# ETHERNET.net
KiCad netlist of a schematic drawn in Altium Designer
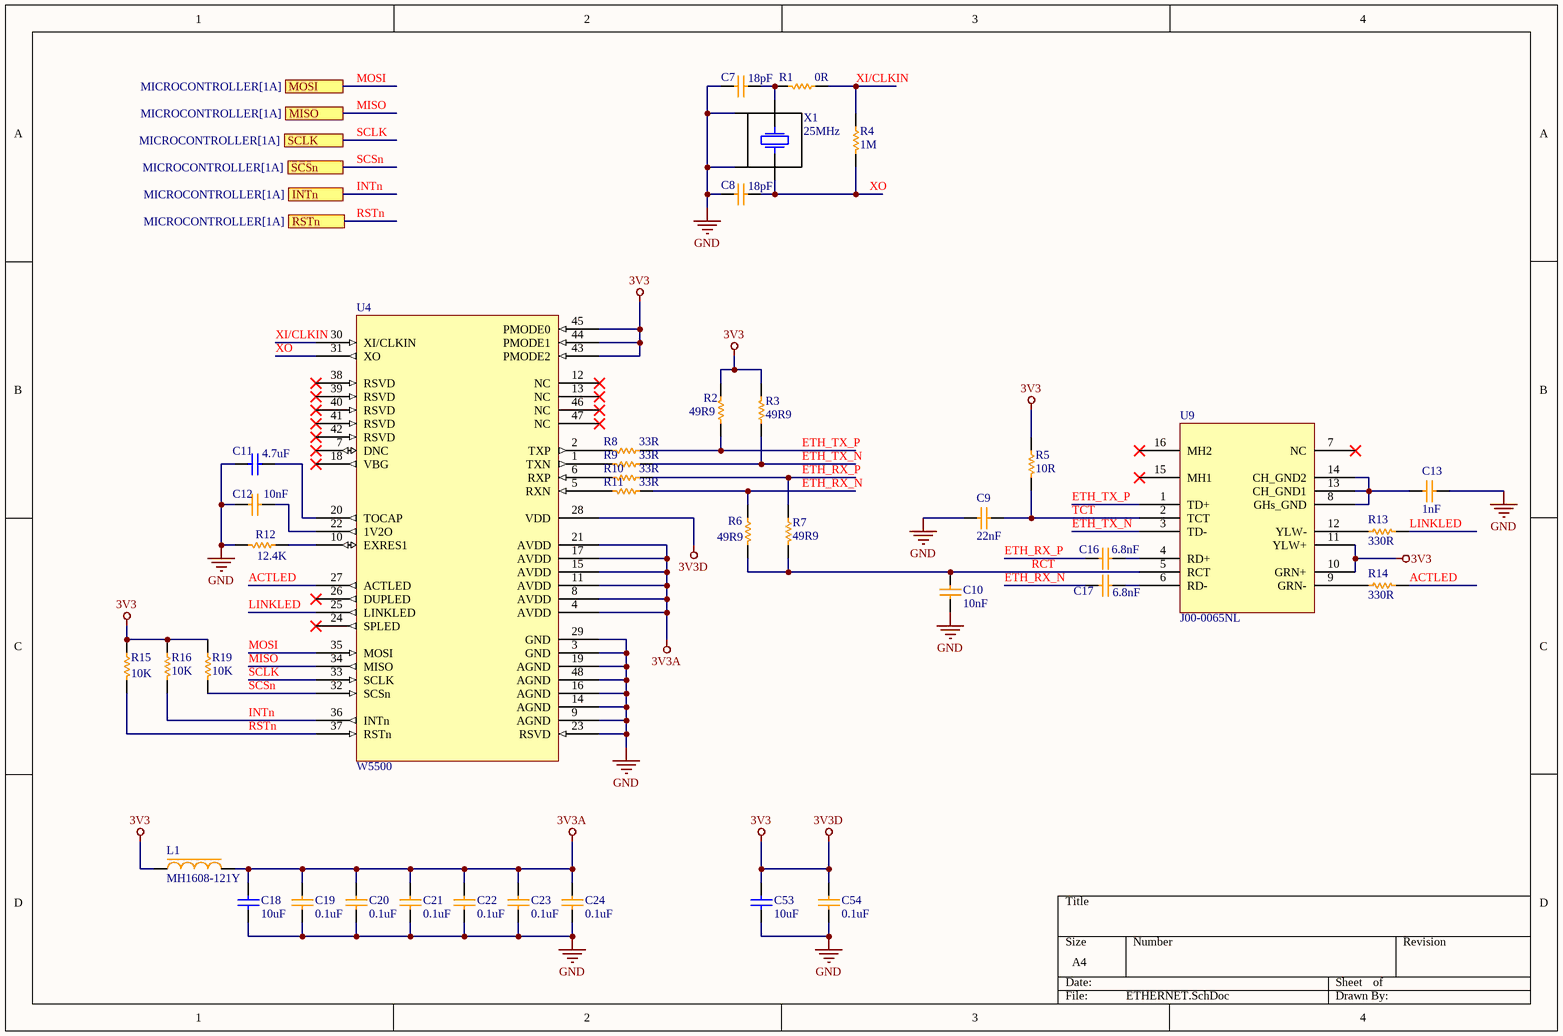
[diagram p0: ETHERNET.SchDoc]

(export (version "E")
  (design (tool "Eeschema 10.0.6"))
  (components
    (comp (ref "C7")
      (value "18pF")
      (footprint "CAP-0603")
      (description "CAP CER 18PF 50V C0G/NP0 0603")
      (libsource (lib "Schlib1") (part "CAP-0603"))
    )
    (comp (ref "C8")
      (value "18pF")
      (footprint "CAP-0603")
      (description "CAP CER 18PF 50V C0G/NP0 0603")
      (libsource (lib "Schlib1") (part "CAP-0603"))
    )
    (comp (ref "C9")
      (value "22nF")
      (footprint "CAP-0603")
      (description "CAP CER 22NF 50V X7R 0603")
      (libsource (lib "Schlib1") (part "CAP-0603"))
    )
    (comp (ref "C10")
      (value "10nF")
      (footprint "CAP-0603")
      (description "CAP CER 1ONF 50V X7R 0603")
      (libsource (lib "Schlib1") (part "CAP-0603"))
    )
    (comp (ref "C11")
      (value "4.7uF")
      (footprint "CAP-0805")
      (description "CAP CER 4.7UF 16V X7R 0805")
      (libsource (lib "Schlib1") (part "CAP-0805"))
    )
    (comp (ref "C12")
      (value "10nF")
      (footprint "CAP-0603")
      (description "CAP CER 1ONF 50V X7R 0603")
      (libsource (lib "Schlib1") (part "CAP-0603"))
    )
    (comp (ref "C13")
      (value "1nF")
      (footprint "CAP-0603")
      (description "CAP CER 1NF 2000V X7R 0603")
      (libsource (lib "Schlib1") (part "CAP-0603"))
    )
    (comp (ref "C16")
      (value "6.8nF")
      (footprint "CAP-0603")
      (description "CAP CER 6800PF 50V X7R 0603")
      (libsource (lib "Schlib1") (part "CAP-0603"))
    )
    (comp (ref "C17")
      (value "6.8nF")
      (footprint "CAP-0603")
      (description "CAP CER 6800PF 50V X7R 0603")
      (libsource (lib "Schlib1") (part "CAP-0603"))
    )
    (comp (ref "C18")
      (value "10uF")
      (footprint "CAP-0805")
      (description "CAP CER 10UF 16V X5R 0805")
      (libsource (lib "Schlib1") (part "CAP-0805"))
    )
    (comp (ref "C19")
      (value "0.1uF")
      (footprint "CAP-0603")
      (description "CAP CER 0.1UF 50V X7R 0603")
      (libsource (lib "Schlib1") (part "CAP-0603"))
    )
    (comp (ref "C20")
      (value "0.1uF")
      (footprint "CAP-0603")
      (description "CAP CER 0.1UF 50V X7R 0603")
      (libsource (lib "Schlib1") (part "CAP-0603"))
    )
    (comp (ref "C21")
      (value "0.1uF")
      (footprint "CAP-0603")
      (description "CAP CER 0.1UF 50V X7R 0603")
      (libsource (lib "Schlib1") (part "CAP-0603"))
    )
    (comp (ref "C22")
      (value "0.1uF")
      (footprint "CAP-0603")
      (description "CAP CER 0.1UF 50V X7R 0603")
      (libsource (lib "Schlib1") (part "CAP-0603"))
    )
    (comp (ref "C23")
      (value "0.1uF")
      (footprint "CAP-0603")
      (description "CAP CER 0.1UF 50V X7R 0603")
      (libsource (lib "Schlib1") (part "CAP-0603"))
    )
    (comp (ref "C24")
      (value "0.1uF")
      (footprint "CAP-0603")
      (description "CAP CER 0.1UF 50V X7R 0603")
      (libsource (lib "Schlib1") (part "CAP-0603"))
    )
    (comp (ref "C53")
      (value "10uF")
      (footprint "CAP-0805")
      (description "CAP CER 10UF 16V X5R 0805")
      (libsource (lib "Schlib1") (part "CAP-0805"))
    )
    (comp (ref "C54")
      (value "0.1uF")
      (footprint "CAP-0603")
      (description "CAP CER 0.1UF 50V X7R 0603")
      (libsource (lib "Schlib1") (part "CAP-0603"))
    )
    (comp (ref "L1")
      (value "MH1608-121Y")
      (footprint "FB-0603")
      (description "FERRITE BEAD 120 OHM 0603 1LN")
      (libsource (lib "schematic") (part "FB-0603"))
    )
    (comp (ref "R1")
      (value "0R")
      (footprint "RES-0603")
      (description "RES SMD 0 OHM JUMPER 1/10W 0603")
      (libsource (lib "Schlib1") (part "RES-0603"))
    )
    (comp (ref "R2")
      (value "49R9")
      (footprint "RES-0603")
      (description "RES SMD 49.9 OHM 1% 1/10W 0603")
      (libsource (lib "Schlib1") (part "RES-0603"))
    )
    (comp (ref "R3")
      (value "49R9")
      (footprint "RES-0603")
      (description "RES SMD 49.9 OHM 1% 1/10W 0603")
      (libsource (lib "Schlib1") (part "RES-0603"))
    )
    (comp (ref "R4")
      (value "1M")
      (footprint "RES-0603")
      (description "RES SMD 1M OHM 1% 1/10W 0603")
      (libsource (lib "Schlib1") (part "RES-0603"))
    )
    (comp (ref "R5")
      (value "10R")
      (footprint "RES-0603")
      (description "RES SMD 10 OHM 1% 1/10W 0603")
      (libsource (lib "Schlib1") (part "RES-0603"))
    )
    (comp (ref "R6")
      (value "49R9")
      (footprint "RES-0603")
      (description "RES SMD 49.9 OHM 1% 1/10W 0603")
      (libsource (lib "Schlib1") (part "RES-0603"))
    )
    (comp (ref "R7")
      (value "49R9")
      (footprint "RES-0603")
      (description "RES SMD 49.9 OHM 1% 1/10W 0603")
      (libsource (lib "Schlib1") (part "RES-0603"))
    )
    (comp (ref "R8")
      (value "33R")
      (footprint "RES-0603")
      (description "RES SMD 33 OHM 1% 1/10W 0603")
      (libsource (lib "Schlib1") (part "RES-0603"))
    )
    (comp (ref "R9")
      (value "33R")
      (footprint "RES-0603")
      (description "RES SMD 33 OHM 1% 1/10W 0603")
      (libsource (lib "Schlib1") (part "RES-0603"))
    )
    (comp (ref "R10")
      (value "33R")
      (footprint "RES-0603")
      (description "RES SMD 33 OHM 1% 1/10W 0603")
      (libsource (lib "Schlib1") (part "RES-0603"))
    )
    (comp (ref "R11")
      (value "33R")
      (footprint "RES-0603")
      (description "RES SMD 33 OHM 1% 1/10W 0603")
      (libsource (lib "Schlib1") (part "RES-0603"))
    )
    (comp (ref "R12")
      (value "12.4K")
      (footprint "RES-0603")
      (description "RES SMD 12.4K OHM 1% 1/10W 0603")
      (libsource (lib "Schlib1") (part "RES-0603"))
    )
    (comp (ref "R13")
      (value "330R")
      (footprint "RES-0603")
      (description "RES SMD 330 OHM 5% 1/10W 0603")
      (libsource (lib "Schlib1") (part "RES-0603"))
    )
    (comp (ref "R14")
      (value "330R")
      (footprint "RES-0603")
      (description "RES SMD 330 OHM 5% 1/10W 0603")
      (libsource (lib "Schlib1") (part "RES-0603"))
    )
    (comp (ref "R15")
      (value "10K")
      (footprint "RES-0603")
      (description "RES SMD 10K OHM 5% 1/10W 0603")
      (libsource (lib "Schlib1") (part "RES-0603"))
    )
    (comp (ref "R16")
      (value "10K")
      (footprint "RES-0603")
      (description "RES SMD 10K OHM 5% 1/10W 0603")
      (libsource (lib "Schlib1") (part "RES-0603"))
    )
    (comp (ref "R19")
      (value "10K")
      (footprint "RES-0603")
      (description "RES SMD 10K OHM 5% 1/10W 0603")
      (libsource (lib "Schlib1") (part "RES-0603"))
    )
    (comp (ref "U4")
      (value "W5500")
      (footprint "48LQFP")
      (description "IC CTLR 3-1 ETH TCP/IP 48LQFP")
      (libsource (lib "schematic") (part "W5500"))
    )
    (comp (ref "U9")
      (value "J00-0065NL")
      (footprint "J00-0065NL")
      (description "CONN JACK 1PORT PCB")
      (libsource (lib "schematic") (part "J00-0065NL"))
    )
    (comp (ref "X1")
      (value "25MHz")
      (footprint "CRYSTAL-2520")
      (description "122M4-25.000F13DWNJK\r\n(2520,25MHz,13pF,10ppm,-40-105,30)")
      (libsource (lib "Schlib1") (part "CRYSTAL-2520"))
    )
  )
  (nets
    (net (code "1") (name "/ACTLED") (class "Default")
      (node (ref "R14") (pin "1") (pinfunction "1_1") (pintype "passive"))
      (node (ref "U4") (pin "27") (pinfunction "ACTLED_27") (pintype "output"))
    )
    (net (code "2") (name "/ETH_RX_N") (class "Default")
      (node (ref "C17") (pin "1") (pinfunction "1_1") (pintype "passive"))
      (node (ref "R11") (pin "2") (pinfunction "2_2") (pintype "passive"))
      (node (ref "R6") (pin "2") (pinfunction "2_2") (pintype "passive"))
    )
    (net (code "3") (name "/ETH_RX_P") (class "Default")
      (node (ref "C16") (pin "1") (pinfunction "1_1") (pintype "passive"))
      (node (ref "R10") (pin "2") (pinfunction "2_2") (pintype "passive"))
      (node (ref "R7") (pin "2") (pinfunction "2_2") (pintype "passive"))
    )
    (net (code "4") (name "/ETH_TX_N") (class "Default")
      (node (ref "R3") (pin "2") (pinfunction "2_2") (pintype "passive"))
      (node (ref "R9") (pin "2") (pinfunction "2_2") (pintype "passive"))
      (node (ref "U9") (pin "3") (pinfunction "TD-_3") (pintype "passive"))
    )
    (net (code "5") (name "/ETH_TX_P") (class "Default")
      (node (ref "R2") (pin "2") (pinfunction "2_2") (pintype "passive"))
      (node (ref "R8") (pin "2") (pinfunction "2_2") (pintype "passive"))
      (node (ref "U9") (pin "1") (pinfunction "TD+_1") (pintype "passive"))
    )
    (net (code "6") (name "/INTn") (class "Default")
      (node (ref "R16") (pin "1") (pinfunction "1_1") (pintype "passive"))
      (node (ref "U4") (pin "36") (pinfunction "INTn_36") (pintype "output"))
    )
    (net (code "7") (name "/LINKLED") (class "Default")
      (node (ref "R13") (pin "1") (pinfunction "1_1") (pintype "passive"))
      (node (ref "U4") (pin "25") (pinfunction "LINKLED_25") (pintype "output"))
    )
    (net (code "8") (name "/MISO") (class "Default")
      (node (ref "U4") (pin "34") (pinfunction "MISO_34") (pintype "output"))
    )
    (net (code "9") (name "/MOSI") (class "Default")
      (node (ref "U4") (pin "35") (pinfunction "MOSI_35") (pintype "input"))
    )
    (net (code "10") (name "/RCT") (class "Default")
      (node (ref "C10") (pin "2") (pinfunction "2_2") (pintype "passive"))
      (node (ref "R6") (pin "1") (pinfunction "1_1") (pintype "passive"))
      (node (ref "R7") (pin "1") (pinfunction "1_1") (pintype "passive"))
      (node (ref "U9") (pin "5") (pinfunction "RCT_5") (pintype "passive"))
    )
    (net (code "11") (name "/RSTn") (class "Default")
      (node (ref "R15") (pin "1") (pinfunction "1_1") (pintype "passive"))
      (node (ref "U4") (pin "37") (pinfunction "RSTn_37") (pintype "input"))
    )
    (net (code "12") (name "/SCLK") (class "Default")
      (node (ref "U4") (pin "33") (pinfunction "SCLK_33") (pintype "input"))
    )
    (net (code "13") (name "/SCSn") (class "Default")
      (node (ref "R19") (pin "1") (pinfunction "1_1") (pintype "passive"))
      (node (ref "U4") (pin "32") (pinfunction "SCSn_32") (pintype "input"))
    )
    (net (code "14") (name "/TCT") (class "Default")
      (node (ref "C9") (pin "1") (pinfunction "1_1") (pintype "passive"))
      (node (ref "R5") (pin "1") (pinfunction "1_1") (pintype "passive"))
      (node (ref "U9") (pin "2") (pinfunction "TCT_2") (pintype "passive"))
    )
    (net (code "15") (name "/XI{slash}CLKIN") (class "Default")
      (node (ref "R1") (pin "2") (pinfunction "2_2") (pintype "passive"))
      (node (ref "R4") (pin "2") (pinfunction "2_2") (pintype "passive"))
      (node (ref "U4") (pin "30") (pinfunction "XI/CLKIN_30") (pintype "input"))
    )
    (net (code "16") (name "/XO") (class "Default")
      (node (ref "C8") (pin "2") (pinfunction "2_2") (pintype "passive"))
      (node (ref "R4") (pin "1") (pinfunction "1_1") (pintype "passive"))
      (node (ref "U4") (pin "31") (pinfunction "XO_31") (pintype "output"))
      (node (ref "X1") (pin "3") (pinfunction "3_3") (pintype "passive"))
    )
    (net (code "17") (name "3V3") (class "Default")
      (node (ref "C53") (pin "2") (pinfunction "2_2") (pintype "passive"))
      (node (ref "C54") (pin "2") (pinfunction "2_2") (pintype "passive"))
      (node (ref "L1") (pin "1") (pinfunction "1_1") (pintype "passive"))
      (node (ref "R15") (pin "2") (pinfunction "2_2") (pintype "passive"))
      (node (ref "R16") (pin "2") (pinfunction "2_2") (pintype "passive"))
      (node (ref "R19") (pin "2") (pinfunction "2_2") (pintype "passive"))
      (node (ref "R2") (pin "1") (pinfunction "1_1") (pintype "passive"))
      (node (ref "R3") (pin "1") (pinfunction "1_1") (pintype "passive"))
      (node (ref "R5") (pin "2") (pinfunction "2_2") (pintype "passive"))
      (node (ref "U4") (pin "28") (pinfunction "VDD_28") (pintype "power_in"))
      (node (ref "U4") (pin "43") (pinfunction "PMODE2_43") (pintype "input"))
      (node (ref "U4") (pin "44") (pinfunction "PMODE1_44") (pintype "input"))
      (node (ref "U4") (pin "45") (pinfunction "PMODE0_45") (pintype "input"))
      (node (ref "U9") (pin "10") (pinfunction "GRN+_10") (pintype "passive"))
      (node (ref "U9") (pin "11") (pinfunction "YLW+_11") (pintype "passive"))
    )
    (net (code "18") (name "3V3A") (class "Default")
      (node (ref "C18") (pin "2") (pinfunction "2_2") (pintype "passive"))
      (node (ref "C19") (pin "2") (pinfunction "2_2") (pintype "passive"))
      (node (ref "C20") (pin "2") (pinfunction "2_2") (pintype "passive"))
      (node (ref "C21") (pin "2") (pinfunction "2_2") (pintype "passive"))
      (node (ref "C22") (pin "2") (pinfunction "2_2") (pintype "passive"))
      (node (ref "C23") (pin "2") (pinfunction "2_2") (pintype "passive"))
      (node (ref "C24") (pin "2") (pinfunction "2_2") (pintype "passive"))
      (node (ref "L1") (pin "2") (pinfunction "2_2") (pintype "passive"))
      (node (ref "U4") (pin "11") (pinfunction "AVDD_11") (pintype "power_in"))
      (node (ref "U4") (pin "15") (pinfunction "AVDD_15") (pintype "power_in"))
      (node (ref "U4") (pin "17") (pinfunction "AVDD_17") (pintype "power_in"))
      (node (ref "U4") (pin "21") (pinfunction "AVDD_21") (pintype "power_in"))
      (node (ref "U4") (pin "4") (pinfunction "AVDD_4") (pintype "power_in"))
      (node (ref "U4") (pin "8") (pinfunction "AVDD_8") (pintype "power_in"))
    )
    (net (code "19") (name "GND") (class "Default")
      (node (ref "C10") (pin "1") (pinfunction "1_1") (pintype "passive"))
      (node (ref "C11") (pin "1") (pinfunction "1_1") (pintype "passive"))
      (node (ref "C12") (pin "2") (pinfunction "2_2") (pintype "passive"))
      (node (ref "C13") (pin "2") (pinfunction "2_2") (pintype "passive"))
      (node (ref "C18") (pin "1") (pinfunction "1_1") (pintype "passive"))
      (node (ref "C19") (pin "1") (pinfunction "1_1") (pintype "passive"))
      (node (ref "C20") (pin "1") (pinfunction "1_1") (pintype "passive"))
      (node (ref "C21") (pin "1") (pinfunction "1_1") (pintype "passive"))
      (node (ref "C22") (pin "1") (pinfunction "1_1") (pintype "passive"))
      (node (ref "C23") (pin "1") (pinfunction "1_1") (pintype "passive"))
      (node (ref "C24") (pin "1") (pinfunction "1_1") (pintype "passive"))
      (node (ref "C53") (pin "1") (pinfunction "1_1") (pintype "passive"))
      (node (ref "C54") (pin "1") (pinfunction "1_1") (pintype "passive"))
      (node (ref "C7") (pin "1") (pinfunction "1_1") (pintype "passive"))
      (node (ref "C8") (pin "1") (pinfunction "1_1") (pintype "passive"))
      (node (ref "C9") (pin "2") (pinfunction "2_2") (pintype "passive"))
      (node (ref "R12") (pin "1") (pinfunction "1_1") (pintype "passive"))
      (node (ref "U4") (pin "14") (pinfunction "AGND_14") (pintype "power_in"))
      (node (ref "U4") (pin "16") (pinfunction "AGND_16") (pintype "power_in"))
      (node (ref "U4") (pin "19") (pinfunction "AGND_19") (pintype "power_in"))
      (node (ref "U4") (pin "23") (pinfunction "RSVD_23") (pintype "input"))
      (node (ref "U4") (pin "29") (pinfunction "GND_29") (pintype "power_in"))
      (node (ref "U4") (pin "3") (pinfunction "GND_3") (pintype "power_in"))
      (node (ref "U4") (pin "48") (pinfunction "AGND_48") (pintype "power_in"))
      (node (ref "U4") (pin "9") (pinfunction "AGND_9") (pintype "power_in"))
      (node (ref "X1") (pin "2") (pinfunction "2_2") (pintype "passive"))
      (node (ref "X1") (pin "4") (pinfunction "4_4") (pintype "passive"))
    )
    (net (code "20") (name "Net-(C7-Pad2)") (class "Default")
      (node (ref "C7") (pin "2") (pinfunction "2_2") (pintype "passive"))
      (node (ref "R1") (pin "1") (pinfunction "1_1") (pintype "passive"))
      (node (ref "X1") (pin "1") (pinfunction "1_1") (pintype "passive"))
    )
    (net (code "21") (name "Net-(U4-1V2O)") (class "Default")
      (node (ref "C12") (pin "1") (pinfunction "1_1") (pintype "passive"))
      (node (ref "U4") (pin "22") (pinfunction "1V2O_22") (pintype "output"))
    )
    (net (code "22") (name "Net-(U4-EXRES1)") (class "Default")
      (node (ref "R12") (pin "2") (pinfunction "2_2") (pintype "passive"))
      (node (ref "U4") (pin "10") (pinfunction "EXRES1_10") (pintype "bidirectional"))
    )
    (net (code "23") (name "Net-(U4-RXN)") (class "Default")
      (node (ref "R11") (pin "1") (pinfunction "1_1") (pintype "passive"))
      (node (ref "U4") (pin "5") (pinfunction "RXN_5") (pintype "input"))
    )
    (net (code "24") (name "Net-(U4-RXP)") (class "Default")
      (node (ref "R10") (pin "1") (pinfunction "1_1") (pintype "passive"))
      (node (ref "U4") (pin "6") (pinfunction "RXP_6") (pintype "input"))
    )
    (net (code "25") (name "Net-(U4-TOCAP)") (class "Default")
      (node (ref "C11") (pin "2") (pinfunction "2_2") (pintype "passive"))
      (node (ref "U4") (pin "20") (pinfunction "TOCAP_20") (pintype "output"))
    )
    (net (code "26") (name "Net-(U4-TXN)") (class "Default")
      (node (ref "R9") (pin "1") (pinfunction "1_1") (pintype "passive"))
      (node (ref "U4") (pin "1") (pinfunction "TXN_1") (pintype "output"))
    )
    (net (code "27") (name "Net-(U4-TXP)") (class "Default")
      (node (ref "R8") (pin "1") (pinfunction "1_1") (pintype "passive"))
      (node (ref "U4") (pin "2") (pinfunction "TXP_2") (pintype "output"))
    )
    (net (code "28") (name "Net-(U9-CH_GND1)") (class "Default")
      (node (ref "C13") (pin "1") (pinfunction "1_1") (pintype "passive"))
      (node (ref "U9") (pin "13") (pinfunction "CH_GND1_13") (pintype "passive"))
      (node (ref "U9") (pin "14") (pinfunction "CH_GND2_14") (pintype "passive"))
      (node (ref "U9") (pin "8") (pinfunction "GHs_GND_8") (pintype "passive"))
    )
    (net (code "29") (name "Net-(U9-GRN-)") (class "Default")
      (node (ref "R14") (pin "2") (pinfunction "2_2") (pintype "passive"))
      (node (ref "U9") (pin "9") (pinfunction "GRN-_9") (pintype "passive"))
    )
    (net (code "30") (name "Net-(U9-RD+)") (class "Default")
      (node (ref "C16") (pin "2") (pinfunction "2_2") (pintype "passive"))
      (node (ref "U9") (pin "4") (pinfunction "RD+_4") (pintype "passive"))
    )
    (net (code "31") (name "Net-(U9-RD-)") (class "Default")
      (node (ref "C17") (pin "2") (pinfunction "2_2") (pintype "passive"))
      (node (ref "U9") (pin "6") (pinfunction "RD-_6") (pintype "passive"))
    )
    (net (code "32") (name "Net-(U9-YLW-)") (class "Default")
      (node (ref "R13") (pin "2") (pinfunction "2_2") (pintype "passive"))
      (node (ref "U9") (pin "12") (pinfunction "YLW-_12") (pintype "passive"))
    )
    (net (code "33") (name "unconnected-(U4-DNC-Pad7)") (class "Default")
      (node (ref "U4") (pin "7") (pinfunction "DNC_7") (pintype "bidirectional+no_connect"))
    )
    (net (code "34") (name "unconnected-(U4-DUPLED-Pad26)") (class "Default")
      (node (ref "U4") (pin "26") (pinfunction "DUPLED_26") (pintype "output+no_connect"))
    )
    (net (code "35") (name "unconnected-(U4-NC-Pad12)") (class "Default")
      (node (ref "U4") (pin "12") (pinfunction "NC_12") (pintype "passive+no_connect"))
    )
    (net (code "36") (name "unconnected-(U4-NC-Pad13)") (class "Default")
      (node (ref "U4") (pin "13") (pinfunction "NC_13") (pintype "passive+no_connect"))
    )
    (net (code "37") (name "unconnected-(U4-NC-Pad46)") (class "Default")
      (node (ref "U4") (pin "46") (pinfunction "NC_46") (pintype "passive+no_connect"))
    )
    (net (code "38") (name "unconnected-(U4-NC-Pad47)") (class "Default")
      (node (ref "U4") (pin "47") (pinfunction "NC_47") (pintype "passive+no_connect"))
    )
    (net (code "39") (name "unconnected-(U4-RSVD-Pad38)") (class "Default")
      (node (ref "U4") (pin "38") (pinfunction "RSVD_38") (pintype "input+no_connect"))
    )
    (net (code "40") (name "unconnected-(U4-RSVD-Pad39)") (class "Default")
      (node (ref "U4") (pin "39") (pinfunction "RSVD_39") (pintype "input+no_connect"))
    )
    (net (code "41") (name "unconnected-(U4-RSVD-Pad40)") (class "Default")
      (node (ref "U4") (pin "40") (pinfunction "RSVD_40") (pintype "input+no_connect"))
    )
    (net (code "42") (name "unconnected-(U4-RSVD-Pad41)") (class "Default")
      (node (ref "U4") (pin "41") (pinfunction "RSVD_41") (pintype "input+no_connect"))
    )
    (net (code "43") (name "unconnected-(U4-RSVD-Pad42)") (class "Default")
      (node (ref "U4") (pin "42") (pinfunction "RSVD_42") (pintype "input+no_connect"))
    )
    (net (code "44") (name "unconnected-(U4-SPLED-Pad24)") (class "Default")
      (node (ref "U4") (pin "24") (pinfunction "SPLED_24") (pintype "output+no_connect"))
    )
    (net (code "45") (name "unconnected-(U4-VBG-Pad18)") (class "Default")
      (node (ref "U4") (pin "18") (pinfunction "VBG_18") (pintype "output+no_connect"))
    )
    (net (code "46") (name "unconnected-(U9-MH1-Pad15)") (class "Default")
      (node (ref "U9") (pin "15") (pinfunction "MH1_15") (pintype "passive+no_connect"))
    )
    (net (code "47") (name "unconnected-(U9-MH2-Pad16)") (class "Default")
      (node (ref "U9") (pin "16") (pinfunction "MH2_16") (pintype "passive+no_connect"))
    )
    (net (code "48") (name "unconnected-(U9-NC-Pad7)") (class "Default")
      (node (ref "U9") (pin "7") (pinfunction "NC_7") (pintype "passive+no_connect"))
    )
  )
)
